# RobotCtrl_V2_Core-board.net
KiCad netlist of a schematic drawn in Altium Designer
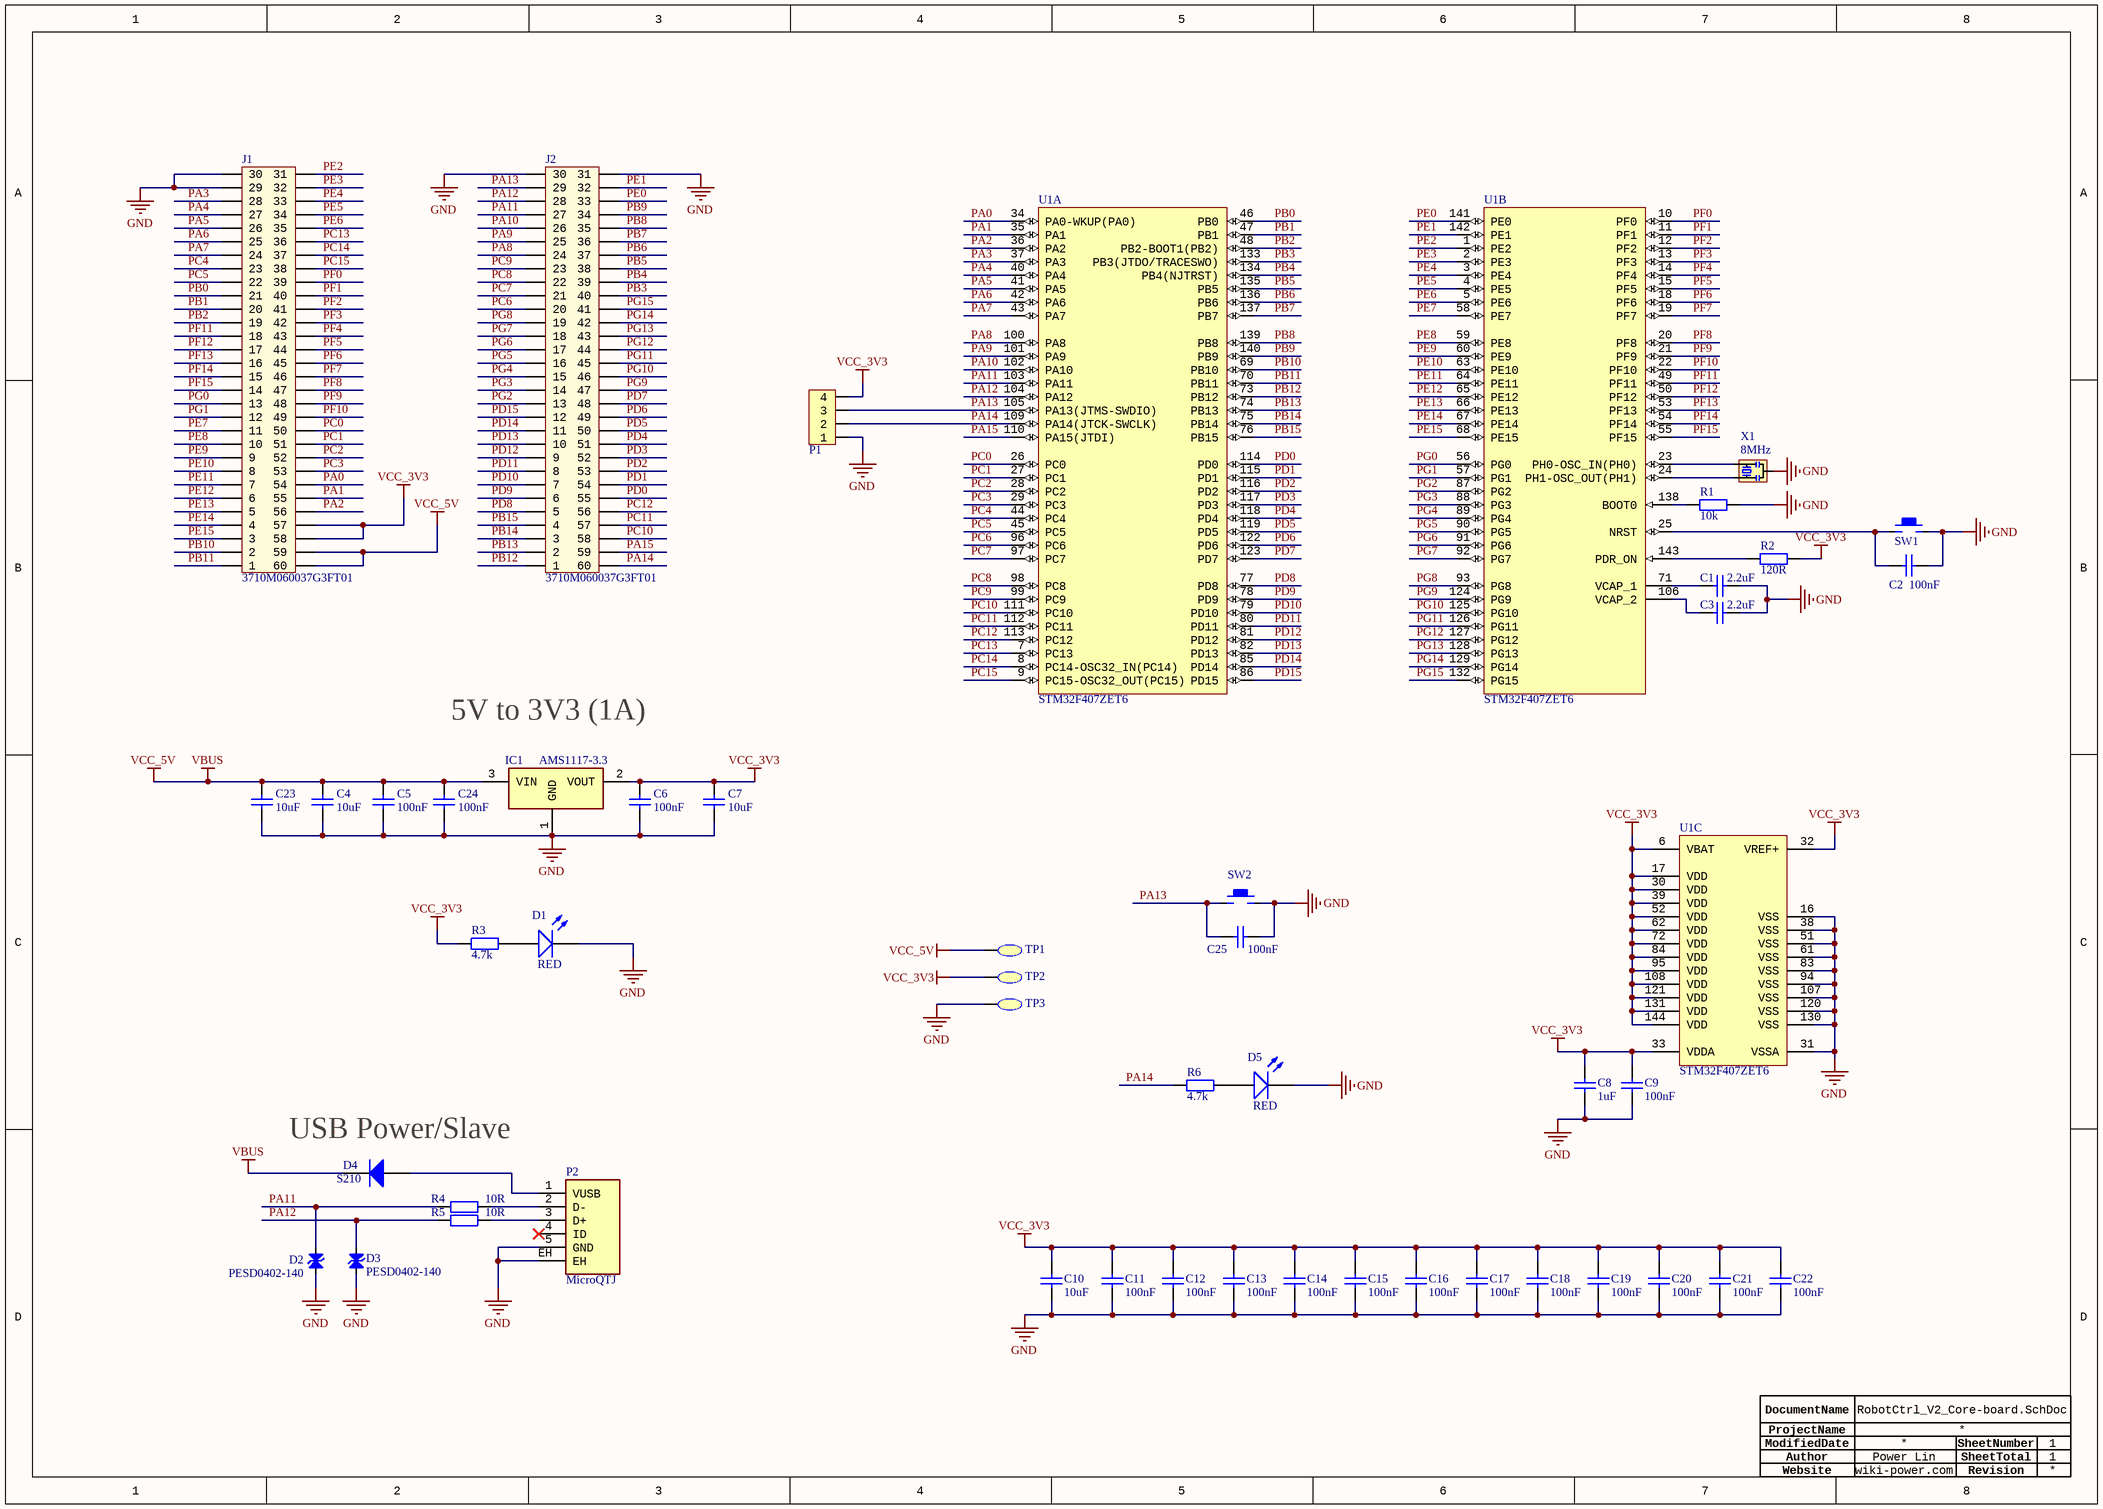
[diagram p0: RobotCtrl_V2_Core-board.SchDoc]

(export (version "E")
  (design (tool "Eeschema 10.0.6"))
  (components
    (comp (ref "C1")
      (value "2.2uF")
      (footprint "CAP-0603")
      (description "贴片电容")
      (libsource (lib "Power_Lib_Altium") (part "CAP"))
    )
    (comp (ref "C2")
      (value "100nF")
      (footprint "CAP-0603")
      (description "贴片电容")
      (libsource (lib "Power_Lib_Altium") (part "CAP"))
    )
    (comp (ref "C3")
      (value "2.2uF")
      (footprint "CAP-0603")
      (description "贴片电容")
      (libsource (lib "Power_Lib_Altium") (part "CAP"))
    )
    (comp (ref "C4")
      (value "10uF")
      (footprint "CAP-0603")
      (description "贴片电容")
      (libsource (lib "Power_Lib_Altium") (part "CAP"))
    )
    (comp (ref "C5")
      (value "100nF")
      (footprint "CAP-0603")
      (description "贴片电容")
      (libsource (lib "Power_Lib_Altium") (part "CAP"))
    )
    (comp (ref "C6")
      (value "100nF")
      (footprint "CAP-0603")
      (description "贴片电容")
      (libsource (lib "Power_Lib_Altium") (part "CAP"))
    )
    (comp (ref "C7")
      (value "10uF")
      (footprint "CAP-0603")
      (description "贴片电容")
      (libsource (lib "Power_Lib_Altium") (part "CAP"))
    )
    (comp (ref "C8")
      (value "1uF")
      (footprint "CAP-0402")
      (description "贴片电容")
      (libsource (lib "Power_Lib_Altium") (part "CAP"))
    )
    (comp (ref "C9")
      (value "100nF")
      (footprint "CAP-0402")
      (description "贴片电容")
      (libsource (lib "Power_Lib_Altium") (part "CAP"))
    )
    (comp (ref "C10")
      (value "10uF")
      (footprint "CAP-0402")
      (description "贴片电容")
      (libsource (lib "Power_Lib_Altium") (part "CAP"))
    )
    (comp (ref "C11")
      (value "100nF")
      (footprint "CAP-0402")
      (description "贴片电容")
      (libsource (lib "Power_Lib_Altium") (part "CAP"))
    )
    (comp (ref "C12")
      (value "100nF")
      (footprint "CAP-0402")
      (description "贴片电容")
      (libsource (lib "Power_Lib_Altium") (part "CAP"))
    )
    (comp (ref "C13")
      (value "100nF")
      (footprint "CAP-0402")
      (description "贴片电容")
      (libsource (lib "Power_Lib_Altium") (part "CAP"))
    )
    (comp (ref "C14")
      (value "100nF")
      (footprint "CAP-0402")
      (description "贴片电容")
      (libsource (lib "Power_Lib_Altium") (part "CAP"))
    )
    (comp (ref "C15")
      (value "100nF")
      (footprint "CAP-0402")
      (description "贴片电容")
      (libsource (lib "Power_Lib_Altium") (part "CAP"))
    )
    (comp (ref "C16")
      (value "100nF")
      (footprint "CAP-0402")
      (description "贴片电容")
      (libsource (lib "Power_Lib_Altium") (part "CAP"))
    )
    (comp (ref "C17")
      (value "100nF")
      (footprint "CAP-0402")
      (description "贴片电容")
      (libsource (lib "Power_Lib_Altium") (part "CAP"))
    )
    (comp (ref "C18")
      (value "100nF")
      (footprint "CAP-0402")
      (description "贴片电容")
      (libsource (lib "Power_Lib_Altium") (part "CAP"))
    )
    (comp (ref "C19")
      (value "100nF")
      (footprint "CAP-0402")
      (description "贴片电容")
      (libsource (lib "Power_Lib_Altium") (part "CAP"))
    )
    (comp (ref "C20")
      (value "100nF")
      (footprint "CAP-0402")
      (description "贴片电容")
      (libsource (lib "Power_Lib_Altium") (part "CAP"))
    )
    (comp (ref "C21")
      (value "100nF")
      (footprint "CAP-0402")
      (description "贴片电容")
      (libsource (lib "Power_Lib_Altium") (part "CAP"))
    )
    (comp (ref "C22")
      (value "100nF")
      (footprint "CAP-0402")
      (description "贴片电容")
      (libsource (lib "Power_Lib_Altium") (part "CAP"))
    )
    (comp (ref "C23")
      (value "10uF")
      (footprint "CAP-0603")
      (description "贴片电容")
      (libsource (lib "Power_Lib_Altium") (part "CAP"))
    )
    (comp (ref "C24")
      (value "100nF")
      (footprint "CAP-0603")
      (description "贴片电容")
      (libsource (lib "Power_Lib_Altium") (part "CAP"))
    )
    (comp (ref "C25")
      (value "100nF")
      (footprint "CAP-0603")
      (description "贴片电容")
      (libsource (lib "Power_Lib_Altium") (part "CAP"))
    )
    (comp (ref "D1")
      (value "RED")
      (footprint "LED-0603")
      (description "发光二极管")
      (libsource (lib "Power_Lib_Altium") (part "LED"))
    )
    (comp (ref "D2")
      (value "PESD0402-140")
      (footprint "D-0402")
      (libsource (lib "Power_Lib_Altium") (part "TVS_C"))
    )
    (comp (ref "D3")
      (value "PESD0402-140")
      (footprint "D-0402")
      (libsource (lib "Power_Lib_Altium") (part "TVS_C"))
    )
    (comp (ref "D4")
      (value "S210")
      (footprint "DO-214AA/SMB")
      (description "二极管")
      (libsource (lib "Power_Lib_Altium") (part "DIODE"))
    )
    (comp (ref "D5")
      (value "RED")
      (footprint "LED-0603")
      (description "发光二极管")
      (libsource (lib "Power_Lib_Altium") (part "LED"))
    )
    (comp (ref "IC1")
      (value "AMS1117-3.3")
      (footprint "SOT-223")
      (description "AMS1117-3.3 1.0A")
      (fields (field (name "MANUFACTURER_PART_NUMBER") "SI2302DS") (field (name "RS PART NUMBER") "7983053P"))
      (libsource (lib "Power_Lib_Altium") (part "AMS1117"))
    )
    (comp (ref "J1")
      (value "3710M060037G3FT01")
      (footprint "3710M060037G3FT01")
      (description "B2B Connector")
      (libsource (lib "Power_Lib_Altium") (part "3710M/F"))
    )
    (comp (ref "J2")
      (value "3710M060037G3FT01")
      (footprint "3710M060037G3FT01")
      (description "B2B Connector")
      (libsource (lib "Power_Lib_Altium") (part "3710M/F"))
    )
    (comp (ref "P1")
      (value "HDR1x4_2.54")
      (footprint "HDR1X4_2.54")
      (description "Header")
      (libsource (lib "Power_Lib_Altium") (part "HDR1x4_2.54"))
    )
    (comp (ref "P2")
      (value "MicroQTJ")
      (footprint "USB-MICRO")
      (description "USB_MICRO")
      (libsource (lib "Power_Lib_Altium") (part "USB_MICRO"))
    )
    (comp (ref "R1")
      (value "10k")
      (footprint "R-0603")
      (description "贴片电阻")
      (libsource (lib "Power_Lib_Altium") (part "RES"))
    )
    (comp (ref "R2")
      (value "120R")
      (footprint "R-0603")
      (description "贴片电阻")
      (libsource (lib "Power_Lib_Altium") (part "RES"))
    )
    (comp (ref "R3")
      (value "4.7k")
      (footprint "R-0603")
      (description "贴片电阻")
      (libsource (lib "Power_Lib_Altium") (part "RES"))
    )
    (comp (ref "R4")
      (value "10R")
      (footprint "R-0603")
      (description "贴片电阻")
      (libsource (lib "") (part "RES_1"))
    )
    (comp (ref "R5")
      (value "10R")
      (footprint "R-0603")
      (description "贴片电阻")
      (libsource (lib "") (part "RES_1"))
    )
    (comp (ref "R6")
      (value "4.7k")
      (footprint "R-0603")
      (description "贴片电阻")
      (libsource (lib "Power_Lib_Altium") (part "RES"))
    )
    (comp (ref "SW1")
      (value "KEY")
      (footprint "KEY-4P-4.2*3.4*2.5")
      (description "按键开关")
      (libsource (lib "Power_Lib_Altium") (part "KEY"))
    )
    (comp (ref "SW2")
      (value "KEY")
      (footprint "KEY-4P-4.2*3.4*2.5")
      (description "按键开关")
      (libsource (lib "Power_Lib_Altium") (part "KEY"))
    )
    (comp (ref "TP1")
      (value "TestPoint")
      (footprint "TestPoint")
      (description "测试点")
      (libsource (lib "Power_Lib_Altium") (part "TestPoint"))
    )
    (comp (ref "TP2")
      (value "TestPoint")
      (footprint "TestPoint")
      (description "测试点")
      (libsource (lib "Power_Lib_Altium") (part "TestPoint"))
    )
    (comp (ref "TP3")
      (value "TestPoint")
      (footprint "TestPoint")
      (description "测试点")
      (libsource (lib "Power_Lib_Altium") (part "TestPoint"))
    )
    (comp (ref "U1")
      (value "STM32F407ZET6")
      (footprint "STM-LQFP144_N")
      (fields (field (name "MANUFACTURER") "STMicroelectronics"))
      (libsource (lib "Power_Lib_Altium") (part "STM32F407ZET6"))
    )
    (comp (ref "X1")
      (value "8MHz")
      (footprint "SMD3213-3P")
      (description "CSTCE8M00G15C99-R0")
      (libsource (lib "Power_Lib_Altium") (part "XTAL"))
    )
  )
  (nets
    (net (code "1") (name "/PA0") (class "Default")
      (node (ref "J1") (pin "54") (pinfunction "54_54") (pintype "passive"))
      (node (ref "U1") (pin "34") (pinfunction "PA0-WKUP(PA0)_34") (pintype "bidirectional"))
    )
    (net (code "2") (name "/PA1") (class "Default")
      (node (ref "J1") (pin "55") (pinfunction "55_55") (pintype "passive"))
      (node (ref "U1") (pin "35") (pinfunction "PA1_35") (pintype "bidirectional"))
    )
    (net (code "3") (name "/PA2") (class "Default")
      (node (ref "J1") (pin "56") (pinfunction "56_56") (pintype "passive"))
      (node (ref "U1") (pin "36") (pinfunction "PA2_36") (pintype "bidirectional"))
    )
    (net (code "4") (name "/PA3") (class "Default")
      (node (ref "J1") (pin "28") (pinfunction "28_28") (pintype "passive"))
      (node (ref "U1") (pin "37") (pinfunction "PA3_37") (pintype "bidirectional"))
    )
    (net (code "5") (name "/PA4") (class "Default")
      (node (ref "J1") (pin "27") (pinfunction "27_27") (pintype "passive"))
      (node (ref "U1") (pin "40") (pinfunction "PA4_40") (pintype "bidirectional"))
    )
    (net (code "6") (name "/PA5") (class "Default")
      (node (ref "J1") (pin "26") (pinfunction "26_26") (pintype "passive"))
      (node (ref "U1") (pin "41") (pinfunction "PA5_41") (pintype "bidirectional"))
    )
    (net (code "7") (name "/PA6") (class "Default")
      (node (ref "J1") (pin "25") (pinfunction "25_25") (pintype "passive"))
      (node (ref "U1") (pin "42") (pinfunction "PA6_42") (pintype "bidirectional"))
    )
    (net (code "8") (name "/PA7") (class "Default")
      (node (ref "J1") (pin "24") (pinfunction "24_24") (pintype "passive"))
      (node (ref "U1") (pin "43") (pinfunction "PA7_43") (pintype "bidirectional"))
    )
    (net (code "9") (name "/PA8") (class "Default")
      (node (ref "J2") (pin "24") (pinfunction "24_24") (pintype "passive"))
      (node (ref "U1") (pin "100") (pinfunction "PA8_100") (pintype "bidirectional"))
    )
    (net (code "10") (name "/PA9") (class "Default")
      (node (ref "J2") (pin "25") (pinfunction "25_25") (pintype "passive"))
      (node (ref "U1") (pin "101") (pinfunction "PA9_101") (pintype "bidirectional"))
    )
    (net (code "11") (name "/PA10") (class "Default")
      (node (ref "J2") (pin "26") (pinfunction "26_26") (pintype "passive"))
      (node (ref "U1") (pin "102") (pinfunction "PA10_102") (pintype "bidirectional"))
    )
    (net (code "12") (name "/PA11") (class "Default")
      (node (ref "D2") (pin "2") (pinfunction "2_2") (pintype "passive"))
      (node (ref "J2") (pin "27") (pinfunction "27_27") (pintype "passive"))
      (node (ref "R4") (pin "1") (pinfunction "1_1") (pintype "passive"))
      (node (ref "U1") (pin "103") (pinfunction "PA11_103") (pintype "bidirectional"))
    )
    (net (code "13") (name "/PA12") (class "Default")
      (node (ref "D3") (pin "2") (pinfunction "2_2") (pintype "passive"))
      (node (ref "J2") (pin "28") (pinfunction "28_28") (pintype "passive"))
      (node (ref "R5") (pin "1") (pinfunction "1_1") (pintype "passive"))
      (node (ref "U1") (pin "104") (pinfunction "PA12_104") (pintype "bidirectional"))
    )
    (net (code "14") (name "/PA13") (class "Default")
      (node (ref "C25") (pin "2") (pinfunction "2_2") (pintype "passive"))
      (node (ref "J2") (pin "29") (pinfunction "29_29") (pintype "passive"))
      (node (ref "P1") (pin "3") (pinfunction "3_3") (pintype "passive"))
      (node (ref "SW2") (pin "1") (pinfunction "1_1") (pintype "passive"))
      (node (ref "U1") (pin "105") (pinfunction "PA13(JTMS-SWDIO)_105") (pintype "bidirectional"))
    )
    (net (code "15") (name "/PA14") (class "Default")
      (node (ref "J2") (pin "60") (pinfunction "60_60") (pintype "passive"))
      (node (ref "P1") (pin "2") (pinfunction "2_2") (pintype "passive"))
      (node (ref "R6") (pin "2") (pinfunction "2_2") (pintype "passive"))
      (node (ref "U1") (pin "109") (pinfunction "PA14(JTCK-SWCLK)_109") (pintype "bidirectional"))
    )
    (net (code "16") (name "/PA15") (class "Default")
      (node (ref "J2") (pin "59") (pinfunction "59_59") (pintype "passive"))
      (node (ref "U1") (pin "110") (pinfunction "PA15(JTDI)_110") (pintype "bidirectional"))
    )
    (net (code "17") (name "/PB0") (class "Default")
      (node (ref "J1") (pin "21") (pinfunction "21_21") (pintype "passive"))
      (node (ref "U1") (pin "46") (pinfunction "PB0_46") (pintype "bidirectional"))
    )
    (net (code "18") (name "/PB1") (class "Default")
      (node (ref "J1") (pin "20") (pinfunction "20_20") (pintype "passive"))
      (node (ref "U1") (pin "47") (pinfunction "PB1_47") (pintype "bidirectional"))
    )
    (net (code "19") (name "/PB2") (class "Default")
      (node (ref "J1") (pin "19") (pinfunction "19_19") (pintype "passive"))
      (node (ref "U1") (pin "48") (pinfunction "PB2-BOOT1(PB2)_48") (pintype "bidirectional"))
    )
    (net (code "20") (name "/PB3") (class "Default")
      (node (ref "J2") (pin "40") (pinfunction "40_40") (pintype "passive"))
      (node (ref "U1") (pin "133") (pinfunction "PB3(JTDO/TRACESWO)_133") (pintype "bidirectional"))
    )
    (net (code "21") (name "/PB4") (class "Default")
      (node (ref "J2") (pin "39") (pinfunction "39_39") (pintype "passive"))
      (node (ref "U1") (pin "134") (pinfunction "PB4(NJTRST)_134") (pintype "bidirectional"))
    )
    (net (code "22") (name "/PB5") (class "Default")
      (node (ref "J2") (pin "38") (pinfunction "38_38") (pintype "passive"))
      (node (ref "U1") (pin "135") (pinfunction "PB5_135") (pintype "bidirectional"))
    )
    (net (code "23") (name "/PB6") (class "Default")
      (node (ref "J2") (pin "37") (pinfunction "37_37") (pintype "passive"))
      (node (ref "U1") (pin "136") (pinfunction "PB6_136") (pintype "bidirectional"))
    )
    (net (code "24") (name "/PB7") (class "Default")
      (node (ref "J2") (pin "36") (pinfunction "36_36") (pintype "passive"))
      (node (ref "U1") (pin "137") (pinfunction "PB7_137") (pintype "bidirectional"))
    )
    (net (code "25") (name "/PB8") (class "Default")
      (node (ref "J2") (pin "35") (pinfunction "35_35") (pintype "passive"))
      (node (ref "U1") (pin "139") (pinfunction "PB8_139") (pintype "bidirectional"))
    )
    (net (code "26") (name "/PB9") (class "Default")
      (node (ref "J2") (pin "34") (pinfunction "34_34") (pintype "passive"))
      (node (ref "U1") (pin "140") (pinfunction "PB9_140") (pintype "bidirectional"))
    )
    (net (code "27") (name "/PB10") (class "Default")
      (node (ref "J1") (pin "2") (pinfunction "2_2") (pintype "passive"))
      (node (ref "U1") (pin "69") (pinfunction "PB10_69") (pintype "bidirectional"))
    )
    (net (code "28") (name "/PB11") (class "Default")
      (node (ref "J1") (pin "1") (pinfunction "1_1") (pintype "passive"))
      (node (ref "U1") (pin "70") (pinfunction "PB11_70") (pintype "bidirectional"))
    )
    (net (code "29") (name "/PB12") (class "Default")
      (node (ref "J2") (pin "1") (pinfunction "1_1") (pintype "passive"))
      (node (ref "U1") (pin "73") (pinfunction "PB12_73") (pintype "bidirectional"))
    )
    (net (code "30") (name "/PB13") (class "Default")
      (node (ref "J2") (pin "2") (pinfunction "2_2") (pintype "passive"))
      (node (ref "U1") (pin "74") (pinfunction "PB13_74") (pintype "bidirectional"))
    )
    (net (code "31") (name "/PB14") (class "Default")
      (node (ref "J2") (pin "3") (pinfunction "3_3") (pintype "passive"))
      (node (ref "U1") (pin "75") (pinfunction "PB14_75") (pintype "bidirectional"))
    )
    (net (code "32") (name "/PB15") (class "Default")
      (node (ref "J2") (pin "4") (pinfunction "4_4") (pintype "passive"))
      (node (ref "U1") (pin "76") (pinfunction "PB15_76") (pintype "bidirectional"))
    )
    (net (code "33") (name "/PC0") (class "Default")
      (node (ref "J1") (pin "50") (pinfunction "50_50") (pintype "passive"))
      (node (ref "U1") (pin "26") (pinfunction "PC0_26") (pintype "bidirectional"))
    )
    (net (code "34") (name "/PC1") (class "Default")
      (node (ref "J1") (pin "51") (pinfunction "51_51") (pintype "passive"))
      (node (ref "U1") (pin "27") (pinfunction "PC1_27") (pintype "bidirectional"))
    )
    (net (code "35") (name "/PC2") (class "Default")
      (node (ref "J1") (pin "52") (pinfunction "52_52") (pintype "passive"))
      (node (ref "U1") (pin "28") (pinfunction "PC2_28") (pintype "bidirectional"))
    )
    (net (code "36") (name "/PC3") (class "Default")
      (node (ref "J1") (pin "53") (pinfunction "53_53") (pintype "passive"))
      (node (ref "U1") (pin "29") (pinfunction "PC3_29") (pintype "bidirectional"))
    )
    (net (code "37") (name "/PC4") (class "Default")
      (node (ref "J1") (pin "23") (pinfunction "23_23") (pintype "passive"))
      (node (ref "U1") (pin "44") (pinfunction "PC4_44") (pintype "bidirectional"))
    )
    (net (code "38") (name "/PC5") (class "Default")
      (node (ref "J1") (pin "22") (pinfunction "22_22") (pintype "passive"))
      (node (ref "U1") (pin "45") (pinfunction "PC5_45") (pintype "bidirectional"))
    )
    (net (code "39") (name "/PC6") (class "Default")
      (node (ref "J2") (pin "20") (pinfunction "20_20") (pintype "passive"))
      (node (ref "U1") (pin "96") (pinfunction "PC6_96") (pintype "bidirectional"))
    )
    (net (code "40") (name "/PC7") (class "Default")
      (node (ref "J2") (pin "21") (pinfunction "21_21") (pintype "passive"))
      (node (ref "U1") (pin "97") (pinfunction "PC7_97") (pintype "bidirectional"))
    )
    (net (code "41") (name "/PC8") (class "Default")
      (node (ref "J2") (pin "22") (pinfunction "22_22") (pintype "passive"))
      (node (ref "U1") (pin "98") (pinfunction "PC8_98") (pintype "bidirectional"))
    )
    (net (code "42") (name "/PC9") (class "Default")
      (node (ref "J2") (pin "23") (pinfunction "23_23") (pintype "passive"))
      (node (ref "U1") (pin "99") (pinfunction "PC9_99") (pintype "bidirectional"))
    )
    (net (code "43") (name "/PC10") (class "Default")
      (node (ref "J2") (pin "58") (pinfunction "58_58") (pintype "passive"))
      (node (ref "U1") (pin "111") (pinfunction "PC10_111") (pintype "bidirectional"))
    )
    (net (code "44") (name "/PC11") (class "Default")
      (node (ref "J2") (pin "57") (pinfunction "57_57") (pintype "passive"))
      (node (ref "U1") (pin "112") (pinfunction "PC11_112") (pintype "bidirectional"))
    )
    (net (code "45") (name "/PC12") (class "Default")
      (node (ref "J2") (pin "56") (pinfunction "56_56") (pintype "passive"))
      (node (ref "U1") (pin "113") (pinfunction "PC12_113") (pintype "bidirectional"))
    )
    (net (code "46") (name "/PC13") (class "Default")
      (node (ref "J1") (pin "36") (pinfunction "36_36") (pintype "passive"))
      (node (ref "U1") (pin "7") (pinfunction "PC13_7") (pintype "bidirectional"))
    )
    (net (code "47") (name "/PC14") (class "Default")
      (node (ref "J1") (pin "37") (pinfunction "37_37") (pintype "passive"))
      (node (ref "U1") (pin "8") (pinfunction "PC14-OSC32_IN(PC14)_8") (pintype "bidirectional"))
    )
    (net (code "48") (name "/PC15") (class "Default")
      (node (ref "J1") (pin "38") (pinfunction "38_38") (pintype "passive"))
      (node (ref "U1") (pin "9") (pinfunction "PC15-OSC32_OUT(PC15)_9") (pintype "bidirectional"))
    )
    (net (code "49") (name "/PD0") (class "Default")
      (node (ref "J2") (pin "55") (pinfunction "55_55") (pintype "passive"))
      (node (ref "U1") (pin "114") (pinfunction "PD0_114") (pintype "bidirectional"))
    )
    (net (code "50") (name "/PD1") (class "Default")
      (node (ref "J2") (pin "54") (pinfunction "54_54") (pintype "passive"))
      (node (ref "U1") (pin "115") (pinfunction "PD1_115") (pintype "bidirectional"))
    )
    (net (code "51") (name "/PD2") (class "Default")
      (node (ref "J2") (pin "53") (pinfunction "53_53") (pintype "passive"))
      (node (ref "U1") (pin "116") (pinfunction "PD2_116") (pintype "bidirectional"))
    )
    (net (code "52") (name "/PD3") (class "Default")
      (node (ref "J2") (pin "52") (pinfunction "52_52") (pintype "passive"))
      (node (ref "U1") (pin "117") (pinfunction "PD3_117") (pintype "bidirectional"))
    )
    (net (code "53") (name "/PD4") (class "Default")
      (node (ref "J2") (pin "51") (pinfunction "51_51") (pintype "passive"))
      (node (ref "U1") (pin "118") (pinfunction "PD4_118") (pintype "bidirectional"))
    )
    (net (code "54") (name "/PD5") (class "Default")
      (node (ref "J2") (pin "50") (pinfunction "50_50") (pintype "passive"))
      (node (ref "U1") (pin "119") (pinfunction "PD5_119") (pintype "bidirectional"))
    )
    (net (code "55") (name "/PD6") (class "Default")
      (node (ref "J2") (pin "49") (pinfunction "49_49") (pintype "passive"))
      (node (ref "U1") (pin "122") (pinfunction "PD6_122") (pintype "bidirectional"))
    )
    (net (code "56") (name "/PD7") (class "Default")
      (node (ref "J2") (pin "48") (pinfunction "48_48") (pintype "passive"))
      (node (ref "U1") (pin "123") (pinfunction "PD7_123") (pintype "bidirectional"))
    )
    (net (code "57") (name "/PD8") (class "Default")
      (node (ref "J2") (pin "5") (pinfunction "5_5") (pintype "passive"))
      (node (ref "U1") (pin "77") (pinfunction "PD8_77") (pintype "bidirectional"))
    )
    (net (code "58") (name "/PD9") (class "Default")
      (node (ref "J2") (pin "6") (pinfunction "6_6") (pintype "passive"))
      (node (ref "U1") (pin "78") (pinfunction "PD9_78") (pintype "bidirectional"))
    )
    (net (code "59") (name "/PD10") (class "Default")
      (node (ref "J2") (pin "7") (pinfunction "7_7") (pintype "passive"))
      (node (ref "U1") (pin "79") (pinfunction "PD10_79") (pintype "bidirectional"))
    )
    (net (code "60") (name "/PD11") (class "Default")
      (node (ref "J2") (pin "8") (pinfunction "8_8") (pintype "passive"))
      (node (ref "U1") (pin "80") (pinfunction "PD11_80") (pintype "bidirectional"))
    )
    (net (code "61") (name "/PD12") (class "Default")
      (node (ref "J2") (pin "9") (pinfunction "9_9") (pintype "passive"))
      (node (ref "U1") (pin "81") (pinfunction "PD12_81") (pintype "bidirectional"))
    )
    (net (code "62") (name "/PD13") (class "Default")
      (node (ref "J2") (pin "10") (pinfunction "10_10") (pintype "passive"))
      (node (ref "U1") (pin "82") (pinfunction "PD13_82") (pintype "bidirectional"))
    )
    (net (code "63") (name "/PD14") (class "Default")
      (node (ref "J2") (pin "11") (pinfunction "11_11") (pintype "passive"))
      (node (ref "U1") (pin "85") (pinfunction "PD14_85") (pintype "bidirectional"))
    )
    (net (code "64") (name "/PD15") (class "Default")
      (node (ref "J2") (pin "12") (pinfunction "12_12") (pintype "passive"))
      (node (ref "U1") (pin "86") (pinfunction "PD15_86") (pintype "bidirectional"))
    )
    (net (code "65") (name "/PE0") (class "Default")
      (node (ref "J2") (pin "33") (pinfunction "33_33") (pintype "passive"))
      (node (ref "U1") (pin "141") (pinfunction "PE0_141") (pintype "bidirectional"))
    )
    (net (code "66") (name "/PE1") (class "Default")
      (node (ref "J2") (pin "32") (pinfunction "32_32") (pintype "passive"))
      (node (ref "U1") (pin "142") (pinfunction "PE1_142") (pintype "bidirectional"))
    )
    (net (code "67") (name "/PE2") (class "Default")
      (node (ref "J1") (pin "31") (pinfunction "31_31") (pintype "passive"))
      (node (ref "U1") (pin "1") (pinfunction "PE2_1") (pintype "bidirectional"))
    )
    (net (code "68") (name "/PE3") (class "Default")
      (node (ref "J1") (pin "32") (pinfunction "32_32") (pintype "passive"))
      (node (ref "U1") (pin "2") (pinfunction "PE3_2") (pintype "bidirectional"))
    )
    (net (code "69") (name "/PE4") (class "Default")
      (node (ref "J1") (pin "33") (pinfunction "33_33") (pintype "passive"))
      (node (ref "U1") (pin "3") (pinfunction "PE4_3") (pintype "bidirectional"))
    )
    (net (code "70") (name "/PE5") (class "Default")
      (node (ref "J1") (pin "34") (pinfunction "34_34") (pintype "passive"))
      (node (ref "U1") (pin "4") (pinfunction "PE5_4") (pintype "bidirectional"))
    )
    (net (code "71") (name "/PE6") (class "Default")
      (node (ref "J1") (pin "35") (pinfunction "35_35") (pintype "passive"))
      (node (ref "U1") (pin "5") (pinfunction "PE6_5") (pintype "bidirectional"))
    )
    (net (code "72") (name "/PE7") (class "Default")
      (node (ref "J1") (pin "11") (pinfunction "11_11") (pintype "passive"))
      (node (ref "U1") (pin "58") (pinfunction "PE7_58") (pintype "bidirectional"))
    )
    (net (code "73") (name "/PE8") (class "Default")
      (node (ref "J1") (pin "10") (pinfunction "10_10") (pintype "passive"))
      (node (ref "U1") (pin "59") (pinfunction "PE8_59") (pintype "bidirectional"))
    )
    (net (code "74") (name "/PE9") (class "Default")
      (node (ref "J1") (pin "9") (pinfunction "9_9") (pintype "passive"))
      (node (ref "U1") (pin "60") (pinfunction "PE9_60") (pintype "bidirectional"))
    )
    (net (code "75") (name "/PE10") (class "Default")
      (node (ref "J1") (pin "8") (pinfunction "8_8") (pintype "passive"))
      (node (ref "U1") (pin "63") (pinfunction "PE10_63") (pintype "bidirectional"))
    )
    (net (code "76") (name "/PE11") (class "Default")
      (node (ref "J1") (pin "7") (pinfunction "7_7") (pintype "passive"))
      (node (ref "U1") (pin "64") (pinfunction "PE11_64") (pintype "bidirectional"))
    )
    (net (code "77") (name "/PE12") (class "Default")
      (node (ref "J1") (pin "6") (pinfunction "6_6") (pintype "passive"))
      (node (ref "U1") (pin "65") (pinfunction "PE12_65") (pintype "bidirectional"))
    )
    (net (code "78") (name "/PE13") (class "Default")
      (node (ref "J1") (pin "5") (pinfunction "5_5") (pintype "passive"))
      (node (ref "U1") (pin "66") (pinfunction "PE13_66") (pintype "bidirectional"))
    )
    (net (code "79") (name "/PE14") (class "Default")
      (node (ref "J1") (pin "4") (pinfunction "4_4") (pintype "passive"))
      (node (ref "U1") (pin "67") (pinfunction "PE14_67") (pintype "bidirectional"))
    )
    (net (code "80") (name "/PE15") (class "Default")
      (node (ref "J1") (pin "3") (pinfunction "3_3") (pintype "passive"))
      (node (ref "U1") (pin "68") (pinfunction "PE15_68") (pintype "bidirectional"))
    )
    (net (code "81") (name "/PF0") (class "Default")
      (node (ref "J1") (pin "39") (pinfunction "39_39") (pintype "passive"))
      (node (ref "U1") (pin "10") (pinfunction "PF0_10") (pintype "bidirectional"))
    )
    (net (code "82") (name "/PF1") (class "Default")
      (node (ref "J1") (pin "40") (pinfunction "40_40") (pintype "passive"))
      (node (ref "U1") (pin "11") (pinfunction "PF1_11") (pintype "bidirectional"))
    )
    (net (code "83") (name "/PF2") (class "Default")
      (node (ref "J1") (pin "41") (pinfunction "41_41") (pintype "passive"))
      (node (ref "U1") (pin "12") (pinfunction "PF2_12") (pintype "bidirectional"))
    )
    (net (code "84") (name "/PF3") (class "Default")
      (node (ref "J1") (pin "42") (pinfunction "42_42") (pintype "passive"))
      (node (ref "U1") (pin "13") (pinfunction "PF3_13") (pintype "bidirectional"))
    )
    (net (code "85") (name "/PF4") (class "Default")
      (node (ref "J1") (pin "43") (pinfunction "43_43") (pintype "passive"))
      (node (ref "U1") (pin "14") (pinfunction "PF4_14") (pintype "bidirectional"))
    )
    (net (code "86") (name "/PF5") (class "Default")
      (node (ref "J1") (pin "44") (pinfunction "44_44") (pintype "passive"))
      (node (ref "U1") (pin "15") (pinfunction "PF5_15") (pintype "bidirectional"))
    )
    (net (code "87") (name "/PF6") (class "Default")
      (node (ref "J1") (pin "45") (pinfunction "45_45") (pintype "passive"))
      (node (ref "U1") (pin "18") (pinfunction "PF6_18") (pintype "bidirectional"))
    )
    (net (code "88") (name "/PF7") (class "Default")
      (node (ref "J1") (pin "46") (pinfunction "46_46") (pintype "passive"))
      (node (ref "U1") (pin "19") (pinfunction "PF7_19") (pintype "bidirectional"))
    )
    (net (code "89") (name "/PF8") (class "Default")
      (node (ref "J1") (pin "47") (pinfunction "47_47") (pintype "passive"))
      (node (ref "U1") (pin "20") (pinfunction "PF8_20") (pintype "bidirectional"))
    )
    (net (code "90") (name "/PF9") (class "Default")
      (node (ref "J1") (pin "48") (pinfunction "48_48") (pintype "passive"))
      (node (ref "U1") (pin "21") (pinfunction "PF9_21") (pintype "bidirectional"))
    )
    (net (code "91") (name "/PF10") (class "Default")
      (node (ref "J1") (pin "49") (pinfunction "49_49") (pintype "passive"))
      (node (ref "U1") (pin "22") (pinfunction "PF10_22") (pintype "bidirectional"))
    )
    (net (code "92") (name "/PF11") (class "Default")
      (node (ref "J1") (pin "18") (pinfunction "18_18") (pintype "passive"))
      (node (ref "U1") (pin "49") (pinfunction "PF11_49") (pintype "bidirectional"))
    )
    (net (code "93") (name "/PF12") (class "Default")
      (node (ref "J1") (pin "17") (pinfunction "17_17") (pintype "passive"))
      (node (ref "U1") (pin "50") (pinfunction "PF12_50") (pintype "bidirectional"))
    )
    (net (code "94") (name "/PF13") (class "Default")
      (node (ref "J1") (pin "16") (pinfunction "16_16") (pintype "passive"))
      (node (ref "U1") (pin "53") (pinfunction "PF13_53") (pintype "bidirectional"))
    )
    (net (code "95") (name "/PF14") (class "Default")
      (node (ref "J1") (pin "15") (pinfunction "15_15") (pintype "passive"))
      (node (ref "U1") (pin "54") (pinfunction "PF14_54") (pintype "bidirectional"))
    )
    (net (code "96") (name "/PF15") (class "Default")
      (node (ref "J1") (pin "14") (pinfunction "14_14") (pintype "passive"))
      (node (ref "U1") (pin "55") (pinfunction "PF15_55") (pintype "bidirectional"))
    )
    (net (code "97") (name "/PG0") (class "Default")
      (node (ref "J1") (pin "13") (pinfunction "13_13") (pintype "passive"))
      (node (ref "U1") (pin "56") (pinfunction "PG0_56") (pintype "bidirectional"))
    )
    (net (code "98") (name "/PG1") (class "Default")
      (node (ref "J1") (pin "12") (pinfunction "12_12") (pintype "passive"))
      (node (ref "U1") (pin "57") (pinfunction "PG1_57") (pintype "bidirectional"))
    )
    (net (code "99") (name "/PG2") (class "Default")
      (node (ref "J2") (pin "13") (pinfunction "13_13") (pintype "passive"))
      (node (ref "U1") (pin "87") (pinfunction "PG2_87") (pintype "bidirectional"))
    )
    (net (code "100") (name "/PG3") (class "Default")
      (node (ref "J2") (pin "14") (pinfunction "14_14") (pintype "passive"))
      (node (ref "U1") (pin "88") (pinfunction "PG3_88") (pintype "bidirectional"))
    )
    (net (code "101") (name "/PG4") (class "Default")
      (node (ref "J2") (pin "15") (pinfunction "15_15") (pintype "passive"))
      (node (ref "U1") (pin "89") (pinfunction "PG4_89") (pintype "bidirectional"))
    )
    (net (code "102") (name "/PG5") (class "Default")
      (node (ref "J2") (pin "16") (pinfunction "16_16") (pintype "passive"))
      (node (ref "U1") (pin "90") (pinfunction "PG5_90") (pintype "bidirectional"))
    )
    (net (code "103") (name "/PG6") (class "Default")
      (node (ref "J2") (pin "17") (pinfunction "17_17") (pintype "passive"))
      (node (ref "U1") (pin "91") (pinfunction "PG6_91") (pintype "bidirectional"))
    )
    (net (code "104") (name "/PG7") (class "Default")
      (node (ref "J2") (pin "18") (pinfunction "18_18") (pintype "passive"))
      (node (ref "U1") (pin "92") (pinfunction "PG7_92") (pintype "bidirectional"))
    )
    (net (code "105") (name "/PG8") (class "Default")
      (node (ref "J2") (pin "19") (pinfunction "19_19") (pintype "passive"))
      (node (ref "U1") (pin "93") (pinfunction "PG8_93") (pintype "bidirectional"))
    )
    (net (code "106") (name "/PG9") (class "Default")
      (node (ref "J2") (pin "47") (pinfunction "47_47") (pintype "passive"))
      (node (ref "U1") (pin "124") (pinfunction "PG9_124") (pintype "bidirectional"))
    )
    (net (code "107") (name "/PG10") (class "Default")
      (node (ref "J2") (pin "46") (pinfunction "46_46") (pintype "passive"))
      (node (ref "U1") (pin "125") (pinfunction "PG10_125") (pintype "bidirectional"))
    )
    (net (code "108") (name "/PG11") (class "Default")
      (node (ref "J2") (pin "45") (pinfunction "45_45") (pintype "passive"))
      (node (ref "U1") (pin "126") (pinfunction "PG11_126") (pintype "bidirectional"))
    )
    (net (code "109") (name "/PG12") (class "Default")
      (node (ref "J2") (pin "44") (pinfunction "44_44") (pintype "passive"))
      (node (ref "U1") (pin "127") (pinfunction "PG12_127") (pintype "bidirectional"))
    )
    (net (code "110") (name "/PG13") (class "Default")
      (node (ref "J2") (pin "43") (pinfunction "43_43") (pintype "passive"))
      (node (ref "U1") (pin "128") (pinfunction "PG13_128") (pintype "bidirectional"))
    )
    (net (code "111") (name "/PG14") (class "Default")
      (node (ref "J2") (pin "42") (pinfunction "42_42") (pintype "passive"))
      (node (ref "U1") (pin "129") (pinfunction "PG14_129") (pintype "bidirectional"))
    )
    (net (code "112") (name "/PG15") (class "Default")
      (node (ref "J2") (pin "41") (pinfunction "41_41") (pintype "passive"))
      (node (ref "U1") (pin "132") (pinfunction "PG15_132") (pintype "bidirectional"))
    )
    (net (code "113") (name "GND") (class "Default")
      (node (ref "C1") (pin "2") (pinfunction "2_2") (pintype "passive"))
      (node (ref "C10") (pin "1") (pinfunction "1_1") (pintype "passive"))
      (node (ref "C11") (pin "1") (pinfunction "1_1") (pintype "passive"))
      (node (ref "C12") (pin "1") (pinfunction "1_1") (pintype "passive"))
      (node (ref "C13") (pin "1") (pinfunction "1_1") (pintype "passive"))
      (node (ref "C14") (pin "1") (pinfunction "1_1") (pintype "passive"))
      (node (ref "C15") (pin "1") (pinfunction "1_1") (pintype "passive"))
      (node (ref "C16") (pin "1") (pinfunction "1_1") (pintype "passive"))
      (node (ref "C17") (pin "1") (pinfunction "1_1") (pintype "passive"))
      (node (ref "C18") (pin "1") (pinfunction "1_1") (pintype "passive"))
      (node (ref "C19") (pin "1") (pinfunction "1_1") (pintype "passive"))
      (node (ref "C2") (pin "1") (pinfunction "1_1") (pintype "passive"))
      (node (ref "C20") (pin "1") (pinfunction "1_1") (pintype "passive"))
      (node (ref "C21") (pin "1") (pinfunction "1_1") (pintype "passive"))
      (node (ref "C22") (pin "1") (pinfunction "1_1") (pintype "passive"))
      (node (ref "C23") (pin "1") (pinfunction "1_1") (pintype "passive"))
      (node (ref "C24") (pin "1") (pinfunction "1_1") (pintype "passive"))
      (node (ref "C25") (pin "1") (pinfunction "1_1") (pintype "passive"))
      (node (ref "C3") (pin "2") (pinfunction "2_2") (pintype "passive"))
      (node (ref "C4") (pin "1") (pinfunction "1_1") (pintype "passive"))
      (node (ref "C5") (pin "1") (pinfunction "1_1") (pintype "passive"))
      (node (ref "C6") (pin "1") (pinfunction "1_1") (pintype "passive"))
      (node (ref "C7") (pin "1") (pinfunction "1_1") (pintype "passive"))
      (node (ref "C8") (pin "1") (pinfunction "1_1") (pintype "passive"))
      (node (ref "C9") (pin "1") (pinfunction "1_1") (pintype "passive"))
      (node (ref "D1") (pin "K") (pinfunction "K_K") (pintype "passive"))
      (node (ref "D2") (pin "1") (pinfunction "1_1") (pintype "passive"))
      (node (ref "D3") (pin "1") (pinfunction "1_1") (pintype "passive"))
      (node (ref "D5") (pin "K") (pinfunction "K_K") (pintype "passive"))
      (node (ref "IC1") (pin "1") (pinfunction "GND_1") (pintype "passive"))
      (node (ref "J1") (pin "29") (pinfunction "29_29") (pintype "passive"))
      (node (ref "J1") (pin "30") (pinfunction "30_30") (pintype "passive"))
      (node (ref "J2") (pin "30") (pinfunction "30_30") (pintype "passive"))
      (node (ref "J2") (pin "31") (pinfunction "31_31") (pintype "passive"))
      (node (ref "P1") (pin "1") (pinfunction "1_1") (pintype "passive"))
      (node (ref "P2") (pin "5") (pinfunction "GND_5") (pintype "passive"))
      (node (ref "P2") (pin "EH") (pinfunction "EH_EH") (pintype "passive"))
      (node (ref "R1") (pin "1") (pinfunction "1_1") (pintype "passive"))
      (node (ref "SW1") (pin "2") (pinfunction "2_2") (pintype "passive"))
      (node (ref "SW2") (pin "2") (pinfunction "2_2") (pintype "passive"))
      (node (ref "TP3") (pin "1") (pinfunction "1_1") (pintype "passive"))
      (node (ref "U1") (pin "107") (pinfunction "VSS_107") (pintype "power_in"))
      (node (ref "U1") (pin "120") (pinfunction "VSS_120") (pintype "power_in"))
      (node (ref "U1") (pin "130") (pinfunction "VSS_130") (pintype "power_in"))
      (node (ref "U1") (pin "16") (pinfunction "VSS_16") (pintype "power_in"))
      (node (ref "U1") (pin "31") (pinfunction "VSSA_31") (pintype "power_in"))
      (node (ref "U1") (pin "38") (pinfunction "VSS_38") (pintype "power_in"))
      (node (ref "U1") (pin "51") (pinfunction "VSS_51") (pintype "power_in"))
      (node (ref "U1") (pin "61") (pinfunction "VSS_61") (pintype "power_in"))
      (node (ref "U1") (pin "83") (pinfunction "VSS_83") (pintype "power_in"))
      (node (ref "U1") (pin "94") (pinfunction "VSS_94") (pintype "power_in"))
      (node (ref "X1") (pin "2") (pinfunction "GND_2") (pintype "passive"))
    )
    (net (code "114") (name "Net-(D1-PadA)") (class "Default")
      (node (ref "D1") (pin "A") (pinfunction "A_A") (pintype "passive"))
      (node (ref "R3") (pin "1") (pinfunction "1_1") (pintype "passive"))
    )
    (net (code "115") (name "Net-(D4-A)") (class "Default")
      (node (ref "D4") (pin "1") (pinfunction "A_1") (pintype "passive"))
      (node (ref "P2") (pin "1") (pinfunction "VUSB_1") (pintype "passive"))
    )
    (net (code "116") (name "Net-(D5-PadA)") (class "Default")
      (node (ref "D5") (pin "A") (pinfunction "A_A") (pintype "passive"))
      (node (ref "R6") (pin "1") (pinfunction "1_1") (pintype "passive"))
    )
    (net (code "117") (name "Net-(P2-D+)") (class "Default")
      (node (ref "P2") (pin "3") (pinfunction "D+_3") (pintype "passive"))
      (node (ref "R5") (pin "2") (pinfunction "2_2") (pintype "passive"))
    )
    (net (code "118") (name "Net-(P2-D-)") (class "Default")
      (node (ref "P2") (pin "2") (pinfunction "D-_2") (pintype "passive"))
      (node (ref "R4") (pin "2") (pinfunction "2_2") (pintype "passive"))
    )
    (net (code "119") (name "Net-(U1B-BOOT0)") (class "Default")
      (node (ref "R1") (pin "2") (pinfunction "2_2") (pintype "passive"))
      (node (ref "U1") (pin "138") (pinfunction "BOOT0_138") (pintype "input"))
    )
    (net (code "120") (name "Net-(U1B-NRST)") (class "Default")
      (node (ref "C2") (pin "2") (pinfunction "2_2") (pintype "passive"))
      (node (ref "SW1") (pin "1") (pinfunction "1_1") (pintype "passive"))
      (node (ref "U1") (pin "25") (pinfunction "NRST_25") (pintype "bidirectional"))
    )
    (net (code "121") (name "Net-(U1B-PDR_ON)") (class "Default")
      (node (ref "R2") (pin "2") (pinfunction "2_2") (pintype "passive"))
      (node (ref "U1") (pin "143") (pinfunction "PDR_ON_143") (pintype "input"))
    )
    (net (code "122") (name "Net-(U1B-PH0-OSC_IN(PH0))") (class "Default")
      (node (ref "U1") (pin "23") (pinfunction "PH0-OSC_IN(PH0)_23") (pintype "bidirectional"))
      (node (ref "X1") (pin "3") (pinfunction "OSC2_3") (pintype "passive"))
    )
    (net (code "123") (name "Net-(U1B-PH1-OSC_OUT(PH1))") (class "Default")
      (node (ref "U1") (pin "24") (pinfunction "PH1-OSC_OUT(PH1)_24") (pintype "bidirectional"))
      (node (ref "X1") (pin "1") (pinfunction "OSC1_1") (pintype "passive"))
    )
    (net (code "124") (name "Net-(U1B-VCAP_1)") (class "Default")
      (node (ref "C1") (pin "1") (pinfunction "1_1") (pintype "passive"))
      (node (ref "U1") (pin "71") (pinfunction "VCAP_1_71") (pintype "power_in"))
    )
    (net (code "125") (name "Net-(U1B-VCAP_2)") (class "Default")
      (node (ref "C3") (pin "1") (pinfunction "1_1") (pintype "passive"))
      (node (ref "U1") (pin "106") (pinfunction "VCAP_2_106") (pintype "power_in"))
    )
    (net (code "126") (name "VBUS") (class "Default")
      (node (ref "C23") (pin "2") (pinfunction "2_2") (pintype "passive"))
      (node (ref "C24") (pin "2") (pinfunction "2_2") (pintype "passive"))
      (node (ref "C4") (pin "2") (pinfunction "2_2") (pintype "passive"))
      (node (ref "C5") (pin "2") (pinfunction "2_2") (pintype "passive"))
      (node (ref "D4") (pin "2") (pinfunction "K_2") (pintype "passive"))
      (node (ref "IC1") (pin "3") (pinfunction "VIN_3") (pintype "passive"))
      (node (ref "J1") (pin "59") (pinfunction "59_59") (pintype "passive"))
      (node (ref "J1") (pin "60") (pinfunction "60_60") (pintype "passive"))
      (node (ref "TP1") (pin "1") (pinfunction "1_1") (pintype "passive"))
    )
    (net (code "127") (name "VCC_3V3") (class "Default")
      (node (ref "C10") (pin "2") (pinfunction "2_2") (pintype "passive"))
      (node (ref "C11") (pin "2") (pinfunction "2_2") (pintype "passive"))
      (node (ref "C12") (pin "2") (pinfunction "2_2") (pintype "passive"))
      (node (ref "C13") (pin "2") (pinfunction "2_2") (pintype "passive"))
      (node (ref "C14") (pin "2") (pinfunction "2_2") (pintype "passive"))
      (node (ref "C15") (pin "2") (pinfunction "2_2") (pintype "passive"))
      (node (ref "C16") (pin "2") (pinfunction "2_2") (pintype "passive"))
      (node (ref "C17") (pin "2") (pinfunction "2_2") (pintype "passive"))
      (node (ref "C18") (pin "2") (pinfunction "2_2") (pintype "passive"))
      (node (ref "C19") (pin "2") (pinfunction "2_2") (pintype "passive"))
      (node (ref "C20") (pin "2") (pinfunction "2_2") (pintype "passive"))
      (node (ref "C21") (pin "2") (pinfunction "2_2") (pintype "passive"))
      (node (ref "C22") (pin "2") (pinfunction "2_2") (pintype "passive"))
      (node (ref "C6") (pin "2") (pinfunction "2_2") (pintype "passive"))
      (node (ref "C7") (pin "2") (pinfunction "2_2") (pintype "passive"))
      (node (ref "C8") (pin "2") (pinfunction "2_2") (pintype "passive"))
      (node (ref "C9") (pin "2") (pinfunction "2_2") (pintype "passive"))
      (node (ref "IC1") (pin "2") (pinfunction "VOUT_2") (pintype "passive"))
      (node (ref "J1") (pin "57") (pinfunction "57_57") (pintype "passive"))
      (node (ref "J1") (pin "58") (pinfunction "58_58") (pintype "passive"))
      (node (ref "P1") (pin "4") (pinfunction "4_4") (pintype "passive"))
      (node (ref "R2") (pin "1") (pinfunction "1_1") (pintype "passive"))
      (node (ref "R3") (pin "2") (pinfunction "2_2") (pintype "passive"))
      (node (ref "TP2") (pin "1") (pinfunction "1_1") (pintype "passive"))
      (node (ref "U1") (pin "108") (pinfunction "VDD_108") (pintype "power_in"))
      (node (ref "U1") (pin "121") (pinfunction "VDD_121") (pintype "power_in"))
      (node (ref "U1") (pin "131") (pinfunction "VDD_131") (pintype "power_in"))
      (node (ref "U1") (pin "144") (pinfunction "VDD_144") (pintype "power_in"))
      (node (ref "U1") (pin "17") (pinfunction "VDD_17") (pintype "power_in"))
      (node (ref "U1") (pin "30") (pinfunction "VDD_30") (pintype "power_in"))
      (node (ref "U1") (pin "32") (pinfunction "VREF+_32") (pintype "power_in"))
      (node (ref "U1") (pin "33") (pinfunction "VDDA_33") (pintype "power_in"))
      (node (ref "U1") (pin "39") (pinfunction "VDD_39") (pintype "power_in"))
      (node (ref "U1") (pin "52") (pinfunction "VDD_52") (pintype "power_in"))
      (node (ref "U1") (pin "6") (pinfunction "VBAT_6") (pintype "power_in"))
      (node (ref "U1") (pin "62") (pinfunction "VDD_62") (pintype "power_in"))
      (node (ref "U1") (pin "72") (pinfunction "VDD_72") (pintype "power_in"))
      (node (ref "U1") (pin "84") (pinfunction "VDD_84") (pintype "power_in"))
      (node (ref "U1") (pin "95") (pinfunction "VDD_95") (pintype "power_in"))
    )
    (net (code "128") (name "unconnected-(P2-ID-Pad4)") (class "Default")
      (node (ref "P2") (pin "4") (pinfunction "ID_4") (pintype "passive+no_connect"))
    )
  )
)
